# input.net
KiCad netlist of a schematic drawn in Altium Designer
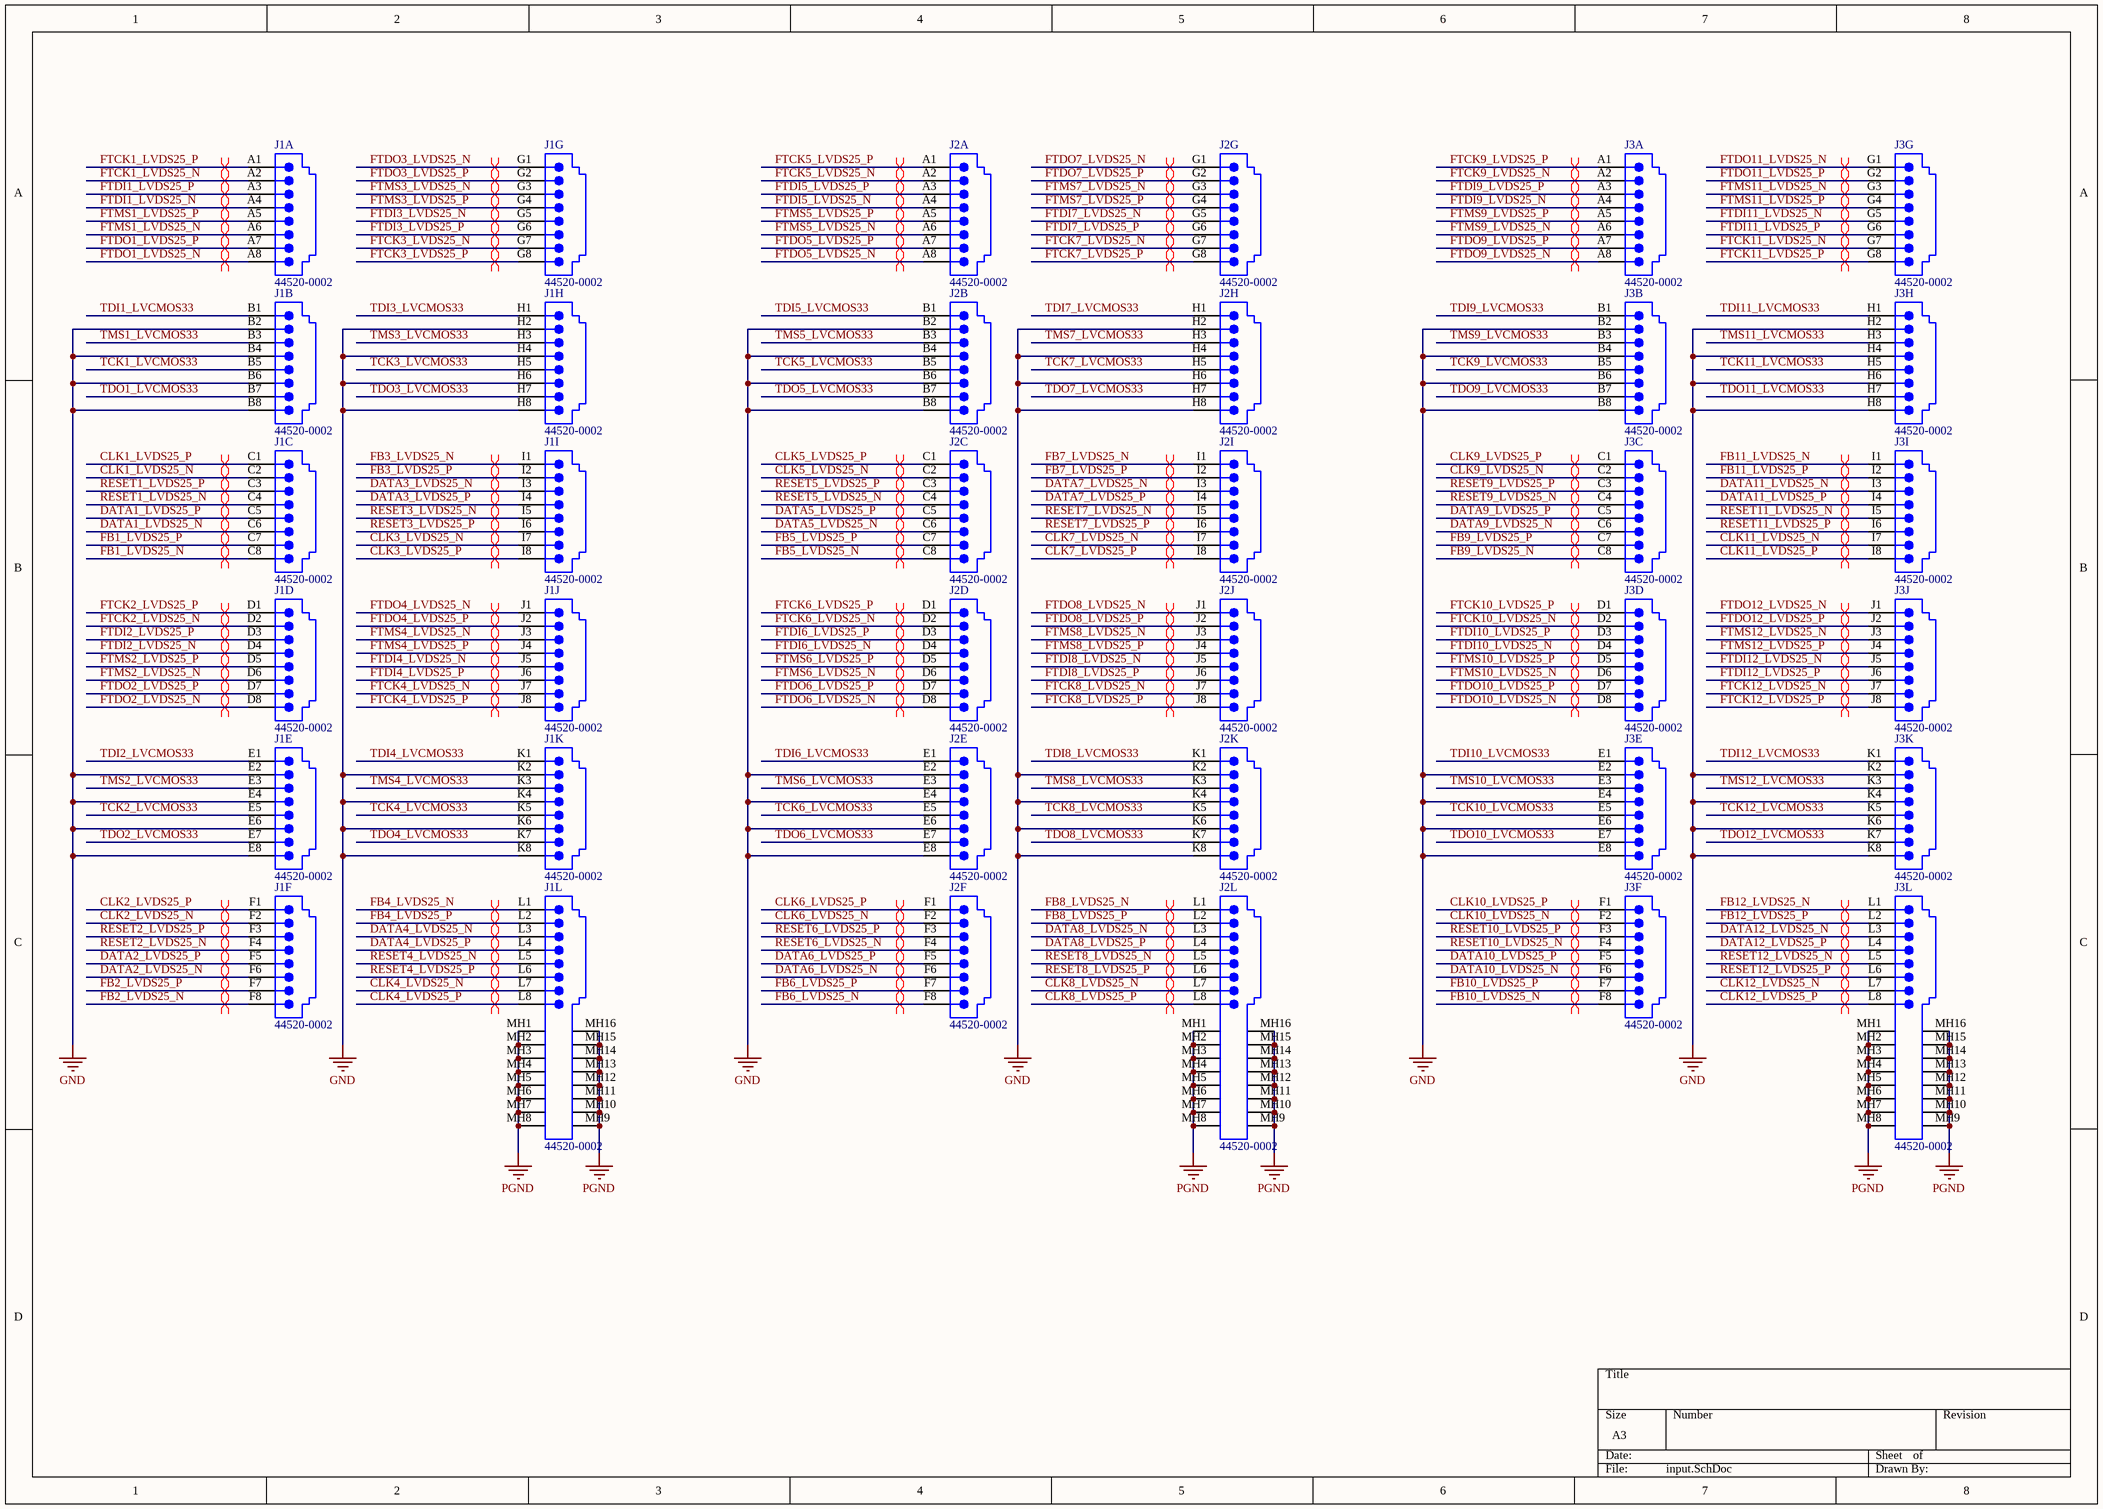
[diagram p0: input.SchDoc]

(export (version "E")
  (design (tool "Eeschema 10.0.6"))
  (components
    (comp (ref "J1")
      (value "44520-0002")
      (footprint "44520-0002")
      (description "High Speed, Stacked, Multi-Port, Right Angle, Snap-Fit, Shielded, Modular Jack")
      (fields (field (name "PUBLISHER") "Altium Limited"))
      (libsource (lib "RJ45大全") (part "44520-0002"))
    )
    (comp (ref "J2")
      (value "44520-0002")
      (footprint "44520-0002")
      (description "High Speed, Stacked, Multi-Port, Right Angle, Snap-Fit, Shielded, Modular Jack")
      (fields (field (name "PUBLISHER") "Altium Limited"))
      (libsource (lib "RJ45大全") (part "44520-0002"))
    )
    (comp (ref "J3")
      (value "44520-0002")
      (footprint "44520-0002")
      (description "High Speed, Stacked, Multi-Port, Right Angle, Snap-Fit, Shielded, Modular Jack")
      (fields (field (name "PUBLISHER") "Altium Limited"))
      (libsource (lib "RJ45大全") (part "44520-0002"))
    )
  )
  (nets
    (net (code "1") (name "/CLK1_LVDS25_N") (class "Default")
      (node (ref "J1") (pin "C2") (pinfunction "C2_C2") (pintype "passive"))
    )
    (net (code "2") (name "/CLK1_LVDS25_P") (class "Default")
      (node (ref "J1") (pin "C1") (pinfunction "C1_C1") (pintype "passive"))
    )
    (net (code "3") (name "/CLK2_LVDS25_N") (class "Default")
      (node (ref "J1") (pin "F2") (pinfunction "F2_F2") (pintype "passive"))
    )
    (net (code "4") (name "/CLK2_LVDS25_P") (class "Default")
      (node (ref "J1") (pin "F1") (pinfunction "F1_F1") (pintype "passive"))
    )
    (net (code "5") (name "/CLK3_LVDS25_N") (class "Default")
      (node (ref "J1") (pin "I7") (pinfunction "I7_I7") (pintype "passive"))
    )
    (net (code "6") (name "/CLK3_LVDS25_P") (class "Default")
      (node (ref "J1") (pin "I8") (pinfunction "I8_I8") (pintype "passive"))
    )
    (net (code "7") (name "/CLK4_LVDS25_N") (class "Default")
      (node (ref "J1") (pin "L7") (pinfunction "L7_L7") (pintype "passive"))
    )
    (net (code "8") (name "/CLK4_LVDS25_P") (class "Default")
      (node (ref "J1") (pin "L8") (pinfunction "L8_L8") (pintype "passive"))
    )
    (net (code "9") (name "/CLK5_LVDS25_N") (class "Default")
      (node (ref "J2") (pin "C2") (pinfunction "C2_C2") (pintype "passive"))
    )
    (net (code "10") (name "/CLK5_LVDS25_P") (class "Default")
      (node (ref "J2") (pin "C1") (pinfunction "C1_C1") (pintype "passive"))
    )
    (net (code "11") (name "/CLK6_LVDS25_N") (class "Default")
      (node (ref "J2") (pin "F2") (pinfunction "F2_F2") (pintype "passive"))
    )
    (net (code "12") (name "/CLK6_LVDS25_P") (class "Default")
      (node (ref "J2") (pin "F1") (pinfunction "F1_F1") (pintype "passive"))
    )
    (net (code "13") (name "/CLK7_LVDS25_N") (class "Default")
      (node (ref "J2") (pin "I7") (pinfunction "I7_I7") (pintype "passive"))
    )
    (net (code "14") (name "/CLK7_LVDS25_P") (class "Default")
      (node (ref "J2") (pin "I8") (pinfunction "I8_I8") (pintype "passive"))
    )
    (net (code "15") (name "/CLK8_LVDS25_N") (class "Default")
      (node (ref "J2") (pin "L7") (pinfunction "L7_L7") (pintype "passive"))
    )
    (net (code "16") (name "/CLK8_LVDS25_P") (class "Default")
      (node (ref "J2") (pin "L8") (pinfunction "L8_L8") (pintype "passive"))
    )
    (net (code "17") (name "/CLK9_LVDS25_N") (class "Default")
      (node (ref "J3") (pin "C2") (pinfunction "C2_C2") (pintype "passive"))
    )
    (net (code "18") (name "/CLK9_LVDS25_P") (class "Default")
      (node (ref "J3") (pin "C1") (pinfunction "C1_C1") (pintype "passive"))
    )
    (net (code "19") (name "/CLK10_LVDS25_N") (class "Default")
      (node (ref "J3") (pin "F2") (pinfunction "F2_F2") (pintype "passive"))
    )
    (net (code "20") (name "/CLK10_LVDS25_P") (class "Default")
      (node (ref "J3") (pin "F1") (pinfunction "F1_F1") (pintype "passive"))
    )
    (net (code "21") (name "/CLK11_LVDS25_N") (class "Default")
      (node (ref "J3") (pin "I7") (pinfunction "I7_I7") (pintype "passive"))
    )
    (net (code "22") (name "/CLK11_LVDS25_P") (class "Default")
      (node (ref "J3") (pin "I8") (pinfunction "I8_I8") (pintype "passive"))
    )
    (net (code "23") (name "/CLK12_LVDS25_N") (class "Default")
      (node (ref "J3") (pin "L7") (pinfunction "L7_L7") (pintype "passive"))
    )
    (net (code "24") (name "/CLK12_LVDS25_P") (class "Default")
      (node (ref "J3") (pin "L8") (pinfunction "L8_L8") (pintype "passive"))
    )
    (net (code "25") (name "/DATA1_LVDS25_N") (class "Default")
      (node (ref "J1") (pin "C6") (pinfunction "C6_C6") (pintype "passive"))
    )
    (net (code "26") (name "/DATA1_LVDS25_P") (class "Default")
      (node (ref "J1") (pin "C5") (pinfunction "C5_C5") (pintype "passive"))
    )
    (net (code "27") (name "/DATA2_LVDS25_N") (class "Default")
      (node (ref "J1") (pin "F6") (pinfunction "F6_F6") (pintype "passive"))
    )
    (net (code "28") (name "/DATA2_LVDS25_P") (class "Default")
      (node (ref "J1") (pin "F5") (pinfunction "F5_F5") (pintype "passive"))
    )
    (net (code "29") (name "/DATA3_LVDS25_N") (class "Default")
      (node (ref "J1") (pin "I3") (pinfunction "I3_I3") (pintype "passive"))
    )
    (net (code "30") (name "/DATA3_LVDS25_P") (class "Default")
      (node (ref "J1") (pin "I4") (pinfunction "I4_I4") (pintype "passive"))
    )
    (net (code "31") (name "/DATA4_LVDS25_N") (class "Default")
      (node (ref "J1") (pin "L3") (pinfunction "L3_L3") (pintype "passive"))
    )
    (net (code "32") (name "/DATA4_LVDS25_P") (class "Default")
      (node (ref "J1") (pin "L4") (pinfunction "L4_L4") (pintype "passive"))
    )
    (net (code "33") (name "/DATA5_LVDS25_N") (class "Default")
      (node (ref "J2") (pin "C6") (pinfunction "C6_C6") (pintype "passive"))
    )
    (net (code "34") (name "/DATA5_LVDS25_P") (class "Default")
      (node (ref "J2") (pin "C5") (pinfunction "C5_C5") (pintype "passive"))
    )
    (net (code "35") (name "/DATA6_LVDS25_N") (class "Default")
      (node (ref "J2") (pin "F6") (pinfunction "F6_F6") (pintype "passive"))
    )
    (net (code "36") (name "/DATA6_LVDS25_P") (class "Default")
      (node (ref "J2") (pin "F5") (pinfunction "F5_F5") (pintype "passive"))
    )
    (net (code "37") (name "/DATA7_LVDS25_N") (class "Default")
      (node (ref "J2") (pin "I3") (pinfunction "I3_I3") (pintype "passive"))
    )
    (net (code "38") (name "/DATA7_LVDS25_P") (class "Default")
      (node (ref "J2") (pin "I4") (pinfunction "I4_I4") (pintype "passive"))
    )
    (net (code "39") (name "/DATA8_LVDS25_N") (class "Default")
      (node (ref "J2") (pin "L3") (pinfunction "L3_L3") (pintype "passive"))
    )
    (net (code "40") (name "/DATA8_LVDS25_P") (class "Default")
      (node (ref "J2") (pin "L4") (pinfunction "L4_L4") (pintype "passive"))
    )
    (net (code "41") (name "/DATA9_LVDS25_N") (class "Default")
      (node (ref "J3") (pin "C6") (pinfunction "C6_C6") (pintype "passive"))
    )
    (net (code "42") (name "/DATA9_LVDS25_P") (class "Default")
      (node (ref "J3") (pin "C5") (pinfunction "C5_C5") (pintype "passive"))
    )
    (net (code "43") (name "/DATA10_LVDS25_N") (class "Default")
      (node (ref "J3") (pin "F6") (pinfunction "F6_F6") (pintype "passive"))
    )
    (net (code "44") (name "/DATA10_LVDS25_P") (class "Default")
      (node (ref "J3") (pin "F5") (pinfunction "F5_F5") (pintype "passive"))
    )
    (net (code "45") (name "/DATA11_LVDS25_N") (class "Default")
      (node (ref "J3") (pin "I3") (pinfunction "I3_I3") (pintype "passive"))
    )
    (net (code "46") (name "/DATA11_LVDS25_P") (class "Default")
      (node (ref "J3") (pin "I4") (pinfunction "I4_I4") (pintype "passive"))
    )
    (net (code "47") (name "/DATA12_LVDS25_N") (class "Default")
      (node (ref "J3") (pin "L3") (pinfunction "L3_L3") (pintype "passive"))
    )
    (net (code "48") (name "/DATA12_LVDS25_P") (class "Default")
      (node (ref "J3") (pin "L4") (pinfunction "L4_L4") (pintype "passive"))
    )
    (net (code "49") (name "/FB1_LVDS25_N") (class "Default")
      (node (ref "J1") (pin "C8") (pinfunction "C8_C8") (pintype "passive"))
    )
    (net (code "50") (name "/FB1_LVDS25_P") (class "Default")
      (node (ref "J1") (pin "C7") (pinfunction "C7_C7") (pintype "passive"))
    )
    (net (code "51") (name "/FB2_LVDS25_N") (class "Default")
      (node (ref "J1") (pin "F8") (pinfunction "F8_F8") (pintype "passive"))
    )
    (net (code "52") (name "/FB2_LVDS25_P") (class "Default")
      (node (ref "J1") (pin "F7") (pinfunction "F7_F7") (pintype "passive"))
    )
    (net (code "53") (name "/FB3_LVDS25_N") (class "Default")
      (node (ref "J1") (pin "I1") (pinfunction "I1_I1") (pintype "passive"))
    )
    (net (code "54") (name "/FB3_LVDS25_P") (class "Default")
      (node (ref "J1") (pin "I2") (pinfunction "I2_I2") (pintype "passive"))
    )
    (net (code "55") (name "/FB4_LVDS25_N") (class "Default")
      (node (ref "J1") (pin "L1") (pinfunction "L1_L1") (pintype "passive"))
    )
    (net (code "56") (name "/FB4_LVDS25_P") (class "Default")
      (node (ref "J1") (pin "L2") (pinfunction "L2_L2") (pintype "passive"))
    )
    (net (code "57") (name "/FB5_LVDS25_N") (class "Default")
      (node (ref "J2") (pin "C8") (pinfunction "C8_C8") (pintype "passive"))
    )
    (net (code "58") (name "/FB5_LVDS25_P") (class "Default")
      (node (ref "J2") (pin "C7") (pinfunction "C7_C7") (pintype "passive"))
    )
    (net (code "59") (name "/FB6_LVDS25_N") (class "Default")
      (node (ref "J2") (pin "F8") (pinfunction "F8_F8") (pintype "passive"))
    )
    (net (code "60") (name "/FB6_LVDS25_P") (class "Default")
      (node (ref "J2") (pin "F7") (pinfunction "F7_F7") (pintype "passive"))
    )
    (net (code "61") (name "/FB7_LVDS25_N") (class "Default")
      (node (ref "J2") (pin "I1") (pinfunction "I1_I1") (pintype "passive"))
    )
    (net (code "62") (name "/FB7_LVDS25_P") (class "Default")
      (node (ref "J2") (pin "I2") (pinfunction "I2_I2") (pintype "passive"))
    )
    (net (code "63") (name "/FB8_LVDS25_N") (class "Default")
      (node (ref "J2") (pin "L1") (pinfunction "L1_L1") (pintype "passive"))
    )
    (net (code "64") (name "/FB8_LVDS25_P") (class "Default")
      (node (ref "J2") (pin "L2") (pinfunction "L2_L2") (pintype "passive"))
    )
    (net (code "65") (name "/FB9_LVDS25_N") (class "Default")
      (node (ref "J3") (pin "C8") (pinfunction "C8_C8") (pintype "passive"))
    )
    (net (code "66") (name "/FB9_LVDS25_P") (class "Default")
      (node (ref "J3") (pin "C7") (pinfunction "C7_C7") (pintype "passive"))
    )
    (net (code "67") (name "/FB10_LVDS25_N") (class "Default")
      (node (ref "J3") (pin "F8") (pinfunction "F8_F8") (pintype "passive"))
    )
    (net (code "68") (name "/FB10_LVDS25_P") (class "Default")
      (node (ref "J3") (pin "F7") (pinfunction "F7_F7") (pintype "passive"))
    )
    (net (code "69") (name "/FB11_LVDS25_N") (class "Default")
      (node (ref "J3") (pin "I1") (pinfunction "I1_I1") (pintype "passive"))
    )
    (net (code "70") (name "/FB11_LVDS25_P") (class "Default")
      (node (ref "J3") (pin "I2") (pinfunction "I2_I2") (pintype "passive"))
    )
    (net (code "71") (name "/FB12_LVDS25_N") (class "Default")
      (node (ref "J3") (pin "L1") (pinfunction "L1_L1") (pintype "passive"))
    )
    (net (code "72") (name "/FB12_LVDS25_P") (class "Default")
      (node (ref "J3") (pin "L2") (pinfunction "L2_L2") (pintype "passive"))
    )
    (net (code "73") (name "/FTCK1_LVDS25_N") (class "Default")
      (node (ref "J1") (pin "A2") (pinfunction "A2_A2") (pintype "passive"))
    )
    (net (code "74") (name "/FTCK1_LVDS25_P") (class "Default")
      (node (ref "J1") (pin "A1") (pinfunction "A1_A1") (pintype "passive"))
    )
    (net (code "75") (name "/FTCK2_LVDS25_N") (class "Default")
      (node (ref "J1") (pin "D2") (pinfunction "D2_D2") (pintype "passive"))
    )
    (net (code "76") (name "/FTCK2_LVDS25_P") (class "Default")
      (node (ref "J1") (pin "D1") (pinfunction "D1_D1") (pintype "passive"))
    )
    (net (code "77") (name "/FTCK3_LVDS25_N") (class "Default")
      (node (ref "J1") (pin "G7") (pinfunction "G7_G7") (pintype "passive"))
    )
    (net (code "78") (name "/FTCK3_LVDS25_P") (class "Default")
      (node (ref "J1") (pin "G8") (pinfunction "G8_G8") (pintype "passive"))
    )
    (net (code "79") (name "/FTCK4_LVDS25_N") (class "Default")
      (node (ref "J1") (pin "J7") (pinfunction "J7_J7") (pintype "passive"))
    )
    (net (code "80") (name "/FTCK4_LVDS25_P") (class "Default")
      (node (ref "J1") (pin "J8") (pinfunction "J8_J8") (pintype "passive"))
    )
    (net (code "81") (name "/FTCK5_LVDS25_N") (class "Default")
      (node (ref "J2") (pin "A2") (pinfunction "A2_A2") (pintype "passive"))
    )
    (net (code "82") (name "/FTCK5_LVDS25_P") (class "Default")
      (node (ref "J2") (pin "A1") (pinfunction "A1_A1") (pintype "passive"))
    )
    (net (code "83") (name "/FTCK6_LVDS25_N") (class "Default")
      (node (ref "J2") (pin "D2") (pinfunction "D2_D2") (pintype "passive"))
    )
    (net (code "84") (name "/FTCK6_LVDS25_P") (class "Default")
      (node (ref "J2") (pin "D1") (pinfunction "D1_D1") (pintype "passive"))
    )
    (net (code "85") (name "/FTCK7_LVDS25_N") (class "Default")
      (node (ref "J2") (pin "G7") (pinfunction "G7_G7") (pintype "passive"))
    )
    (net (code "86") (name "/FTCK7_LVDS25_P") (class "Default")
      (node (ref "J2") (pin "G8") (pinfunction "G8_G8") (pintype "passive"))
    )
    (net (code "87") (name "/FTCK8_LVDS25_N") (class "Default")
      (node (ref "J2") (pin "J7") (pinfunction "J7_J7") (pintype "passive"))
    )
    (net (code "88") (name "/FTCK8_LVDS25_P") (class "Default")
      (node (ref "J2") (pin "J8") (pinfunction "J8_J8") (pintype "passive"))
    )
    (net (code "89") (name "/FTCK9_LVDS25_N") (class "Default")
      (node (ref "J3") (pin "A2") (pinfunction "A2_A2") (pintype "passive"))
    )
    (net (code "90") (name "/FTCK9_LVDS25_P") (class "Default")
      (node (ref "J3") (pin "A1") (pinfunction "A1_A1") (pintype "passive"))
    )
    (net (code "91") (name "/FTCK10_LVDS25_N") (class "Default")
      (node (ref "J3") (pin "D2") (pinfunction "D2_D2") (pintype "passive"))
    )
    (net (code "92") (name "/FTCK10_LVDS25_P") (class "Default")
      (node (ref "J3") (pin "D1") (pinfunction "D1_D1") (pintype "passive"))
    )
    (net (code "93") (name "/FTCK11_LVDS25_N") (class "Default")
      (node (ref "J3") (pin "G7") (pinfunction "G7_G7") (pintype "passive"))
    )
    (net (code "94") (name "/FTCK11_LVDS25_P") (class "Default")
      (node (ref "J3") (pin "G8") (pinfunction "G8_G8") (pintype "passive"))
    )
    (net (code "95") (name "/FTCK12_LVDS25_N") (class "Default")
      (node (ref "J3") (pin "J7") (pinfunction "J7_J7") (pintype "passive"))
    )
    (net (code "96") (name "/FTCK12_LVDS25_P") (class "Default")
      (node (ref "J3") (pin "J8") (pinfunction "J8_J8") (pintype "passive"))
    )
    (net (code "97") (name "/FTDI1_LVDS25_N") (class "Default")
      (node (ref "J1") (pin "A4") (pinfunction "A4_A4") (pintype "passive"))
    )
    (net (code "98") (name "/FTDI1_LVDS25_P") (class "Default")
      (node (ref "J1") (pin "A3") (pinfunction "A3_A3") (pintype "passive"))
    )
    (net (code "99") (name "/FTDI2_LVDS25_N") (class "Default")
      (node (ref "J1") (pin "D4") (pinfunction "D4_D4") (pintype "passive"))
    )
    (net (code "100") (name "/FTDI2_LVDS25_P") (class "Default")
      (node (ref "J1") (pin "D3") (pinfunction "D3_D3") (pintype "passive"))
    )
    (net (code "101") (name "/FTDI3_LVDS25_N") (class "Default")
      (node (ref "J1") (pin "G5") (pinfunction "G5_G5") (pintype "passive"))
    )
    (net (code "102") (name "/FTDI3_LVDS25_P") (class "Default")
      (node (ref "J1") (pin "G6") (pinfunction "G6_G6") (pintype "passive"))
    )
    (net (code "103") (name "/FTDI4_LVDS25_N") (class "Default")
      (node (ref "J1") (pin "J5") (pinfunction "J5_J5") (pintype "passive"))
    )
    (net (code "104") (name "/FTDI4_LVDS25_P") (class "Default")
      (node (ref "J1") (pin "J6") (pinfunction "J6_J6") (pintype "passive"))
    )
    (net (code "105") (name "/FTDI5_LVDS25_N") (class "Default")
      (node (ref "J2") (pin "A4") (pinfunction "A4_A4") (pintype "passive"))
    )
    (net (code "106") (name "/FTDI5_LVDS25_P") (class "Default")
      (node (ref "J2") (pin "A3") (pinfunction "A3_A3") (pintype "passive"))
    )
    (net (code "107") (name "/FTDI6_LVDS25_N") (class "Default")
      (node (ref "J2") (pin "D4") (pinfunction "D4_D4") (pintype "passive"))
    )
    (net (code "108") (name "/FTDI6_LVDS25_P") (class "Default")
      (node (ref "J2") (pin "D3") (pinfunction "D3_D3") (pintype "passive"))
    )
    (net (code "109") (name "/FTDI7_LVDS25_N") (class "Default")
      (node (ref "J2") (pin "G5") (pinfunction "G5_G5") (pintype "passive"))
    )
    (net (code "110") (name "/FTDI7_LVDS25_P") (class "Default")
      (node (ref "J2") (pin "G6") (pinfunction "G6_G6") (pintype "passive"))
    )
    (net (code "111") (name "/FTDI8_LVDS25_N") (class "Default")
      (node (ref "J2") (pin "J5") (pinfunction "J5_J5") (pintype "passive"))
    )
    (net (code "112") (name "/FTDI8_LVDS25_P") (class "Default")
      (node (ref "J2") (pin "J6") (pinfunction "J6_J6") (pintype "passive"))
    )
    (net (code "113") (name "/FTDI9_LVDS25_N") (class "Default")
      (node (ref "J3") (pin "A4") (pinfunction "A4_A4") (pintype "passive"))
    )
    (net (code "114") (name "/FTDI9_LVDS25_P") (class "Default")
      (node (ref "J3") (pin "A3") (pinfunction "A3_A3") (pintype "passive"))
    )
    (net (code "115") (name "/FTDI10_LVDS25_N") (class "Default")
      (node (ref "J3") (pin "D4") (pinfunction "D4_D4") (pintype "passive"))
    )
    (net (code "116") (name "/FTDI10_LVDS25_P") (class "Default")
      (node (ref "J3") (pin "D3") (pinfunction "D3_D3") (pintype "passive"))
    )
    (net (code "117") (name "/FTDI11_LVDS25_N") (class "Default")
      (node (ref "J3") (pin "G5") (pinfunction "G5_G5") (pintype "passive"))
    )
    (net (code "118") (name "/FTDI11_LVDS25_P") (class "Default")
      (node (ref "J3") (pin "G6") (pinfunction "G6_G6") (pintype "passive"))
    )
    (net (code "119") (name "/FTDI12_LVDS25_N") (class "Default")
      (node (ref "J3") (pin "J5") (pinfunction "J5_J5") (pintype "passive"))
    )
    (net (code "120") (name "/FTDI12_LVDS25_P") (class "Default")
      (node (ref "J3") (pin "J6") (pinfunction "J6_J6") (pintype "passive"))
    )
    (net (code "121") (name "/FTDO1_LVDS25_N") (class "Default")
      (node (ref "J1") (pin "A8") (pinfunction "A8_A8") (pintype "passive"))
    )
    (net (code "122") (name "/FTDO1_LVDS25_P") (class "Default")
      (node (ref "J1") (pin "A7") (pinfunction "A7_A7") (pintype "passive"))
    )
    (net (code "123") (name "/FTDO2_LVDS25_N") (class "Default")
      (node (ref "J1") (pin "D8") (pinfunction "D8_D8") (pintype "passive"))
    )
    (net (code "124") (name "/FTDO2_LVDS25_P") (class "Default")
      (node (ref "J1") (pin "D7") (pinfunction "D7_D7") (pintype "passive"))
    )
    (net (code "125") (name "/FTDO3_LVDS25_N") (class "Default")
      (node (ref "J1") (pin "G1") (pinfunction "G1_G1") (pintype "passive"))
    )
    (net (code "126") (name "/FTDO3_LVDS25_P") (class "Default")
      (node (ref "J1") (pin "G2") (pinfunction "G2_G2") (pintype "passive"))
    )
    (net (code "127") (name "/FTDO4_LVDS25_N") (class "Default")
      (node (ref "J1") (pin "J1") (pinfunction "J1_J1") (pintype "passive"))
    )
    (net (code "128") (name "/FTDO4_LVDS25_P") (class "Default")
      (node (ref "J1") (pin "J2") (pinfunction "J2_J2") (pintype "passive"))
    )
    (net (code "129") (name "/FTDO5_LVDS25_N") (class "Default")
      (node (ref "J2") (pin "A8") (pinfunction "A8_A8") (pintype "passive"))
    )
    (net (code "130") (name "/FTDO5_LVDS25_P") (class "Default")
      (node (ref "J2") (pin "A7") (pinfunction "A7_A7") (pintype "passive"))
    )
    (net (code "131") (name "/FTDO6_LVDS25_N") (class "Default")
      (node (ref "J2") (pin "D8") (pinfunction "D8_D8") (pintype "passive"))
    )
    (net (code "132") (name "/FTDO6_LVDS25_P") (class "Default")
      (node (ref "J2") (pin "D7") (pinfunction "D7_D7") (pintype "passive"))
    )
    (net (code "133") (name "/FTDO7_LVDS25_N") (class "Default")
      (node (ref "J2") (pin "G1") (pinfunction "G1_G1") (pintype "passive"))
    )
    (net (code "134") (name "/FTDO7_LVDS25_P") (class "Default")
      (node (ref "J2") (pin "G2") (pinfunction "G2_G2") (pintype "passive"))
    )
    (net (code "135") (name "/FTDO8_LVDS25_N") (class "Default")
      (node (ref "J2") (pin "J1") (pinfunction "J1_J1") (pintype "passive"))
    )
    (net (code "136") (name "/FTDO8_LVDS25_P") (class "Default")
      (node (ref "J2") (pin "J2") (pinfunction "J2_J2") (pintype "passive"))
    )
    (net (code "137") (name "/FTDO9_LVDS25_N") (class "Default")
      (node (ref "J3") (pin "A8") (pinfunction "A8_A8") (pintype "passive"))
    )
    (net (code "138") (name "/FTDO9_LVDS25_P") (class "Default")
      (node (ref "J3") (pin "A7") (pinfunction "A7_A7") (pintype "passive"))
    )
    (net (code "139") (name "/FTDO10_LVDS25_N") (class "Default")
      (node (ref "J3") (pin "D8") (pinfunction "D8_D8") (pintype "passive"))
    )
    (net (code "140") (name "/FTDO10_LVDS25_P") (class "Default")
      (node (ref "J3") (pin "D7") (pinfunction "D7_D7") (pintype "passive"))
    )
    (net (code "141") (name "/FTDO11_LVDS25_N") (class "Default")
      (node (ref "J3") (pin "G1") (pinfunction "G1_G1") (pintype "passive"))
    )
    (net (code "142") (name "/FTDO11_LVDS25_P") (class "Default")
      (node (ref "J3") (pin "G2") (pinfunction "G2_G2") (pintype "passive"))
    )
    (net (code "143") (name "/FTDO12_LVDS25_N") (class "Default")
      (node (ref "J3") (pin "J1") (pinfunction "J1_J1") (pintype "passive"))
    )
    (net (code "144") (name "/FTDO12_LVDS25_P") (class "Default")
      (node (ref "J3") (pin "J2") (pinfunction "J2_J2") (pintype "passive"))
    )
    (net (code "145") (name "/FTMS1_LVDS25_N") (class "Default")
      (node (ref "J1") (pin "A6") (pinfunction "A6_A6") (pintype "passive"))
    )
    (net (code "146") (name "/FTMS1_LVDS25_P") (class "Default")
      (node (ref "J1") (pin "A5") (pinfunction "A5_A5") (pintype "passive"))
    )
    (net (code "147") (name "/FTMS2_LVDS25_N") (class "Default")
      (node (ref "J1") (pin "D6") (pinfunction "D6_D6") (pintype "passive"))
    )
    (net (code "148") (name "/FTMS2_LVDS25_P") (class "Default")
      (node (ref "J1") (pin "D5") (pinfunction "D5_D5") (pintype "passive"))
    )
    (net (code "149") (name "/FTMS3_LVDS25_N") (class "Default")
      (node (ref "J1") (pin "G3") (pinfunction "G3_G3") (pintype "passive"))
    )
    (net (code "150") (name "/FTMS3_LVDS25_P") (class "Default")
      (node (ref "J1") (pin "G4") (pinfunction "G4_G4") (pintype "passive"))
    )
    (net (code "151") (name "/FTMS4_LVDS25_N") (class "Default")
      (node (ref "J1") (pin "J3") (pinfunction "J3_J3") (pintype "passive"))
    )
    (net (code "152") (name "/FTMS4_LVDS25_P") (class "Default")
      (node (ref "J1") (pin "J4") (pinfunction "J4_J4") (pintype "passive"))
    )
    (net (code "153") (name "/FTMS5_LVDS25_N") (class "Default")
      (node (ref "J2") (pin "A6") (pinfunction "A6_A6") (pintype "passive"))
    )
    (net (code "154") (name "/FTMS5_LVDS25_P") (class "Default")
      (node (ref "J2") (pin "A5") (pinfunction "A5_A5") (pintype "passive"))
    )
    (net (code "155") (name "/FTMS6_LVDS25_N") (class "Default")
      (node (ref "J2") (pin "D6") (pinfunction "D6_D6") (pintype "passive"))
    )
    (net (code "156") (name "/FTMS6_LVDS25_P") (class "Default")
      (node (ref "J2") (pin "D5") (pinfunction "D5_D5") (pintype "passive"))
    )
    (net (code "157") (name "/FTMS7_LVDS25_N") (class "Default")
      (node (ref "J2") (pin "G3") (pinfunction "G3_G3") (pintype "passive"))
    )
    (net (code "158") (name "/FTMS7_LVDS25_P") (class "Default")
      (node (ref "J2") (pin "G4") (pinfunction "G4_G4") (pintype "passive"))
    )
    (net (code "159") (name "/FTMS8_LVDS25_N") (class "Default")
      (node (ref "J2") (pin "J3") (pinfunction "J3_J3") (pintype "passive"))
    )
    (net (code "160") (name "/FTMS8_LVDS25_P") (class "Default")
      (node (ref "J2") (pin "J4") (pinfunction "J4_J4") (pintype "passive"))
    )
    (net (code "161") (name "/FTMS9_LVDS25_N") (class "Default")
      (node (ref "J3") (pin "A6") (pinfunction "A6_A6") (pintype "passive"))
    )
    (net (code "162") (name "/FTMS9_LVDS25_P") (class "Default")
      (node (ref "J3") (pin "A5") (pinfunction "A5_A5") (pintype "passive"))
    )
    (net (code "163") (name "/FTMS10_LVDS25_N") (class "Default")
      (node (ref "J3") (pin "D6") (pinfunction "D6_D6") (pintype "passive"))
    )
    (net (code "164") (name "/FTMS10_LVDS25_P") (class "Default")
      (node (ref "J3") (pin "D5") (pinfunction "D5_D5") (pintype "passive"))
    )
    (net (code "165") (name "/FTMS11_LVDS25_N") (class "Default")
      (node (ref "J3") (pin "G3") (pinfunction "G3_G3") (pintype "passive"))
    )
    (net (code "166") (name "/FTMS11_LVDS25_P") (class "Default")
      (node (ref "J3") (pin "G4") (pinfunction "G4_G4") (pintype "passive"))
    )
    (net (code "167") (name "/FTMS12_LVDS25_N") (class "Default")
      (node (ref "J3") (pin "J3") (pinfunction "J3_J3") (pintype "passive"))
    )
    (net (code "168") (name "/FTMS12_LVDS25_P") (class "Default")
      (node (ref "J3") (pin "J4") (pinfunction "J4_J4") (pintype "passive"))
    )
    (net (code "169") (name "/RESET1_LVDS25_N") (class "Default")
      (node (ref "J1") (pin "C4") (pinfunction "C4_C4") (pintype "passive"))
    )
    (net (code "170") (name "/RESET1_LVDS25_P") (class "Default")
      (node (ref "J1") (pin "C3") (pinfunction "C3_C3") (pintype "passive"))
    )
    (net (code "171") (name "/RESET2_LVDS25_N") (class "Default")
      (node (ref "J1") (pin "F4") (pinfunction "F4_F4") (pintype "passive"))
    )
    (net (code "172") (name "/RESET2_LVDS25_P") (class "Default")
      (node (ref "J1") (pin "F3") (pinfunction "F3_F3") (pintype "passive"))
    )
    (net (code "173") (name "/RESET3_LVDS25_N") (class "Default")
      (node (ref "J1") (pin "I5") (pinfunction "I5_I5") (pintype "passive"))
    )
    (net (code "174") (name "/RESET3_LVDS25_P") (class "Default")
      (node (ref "J1") (pin "I6") (pinfunction "I6_I6") (pintype "passive"))
    )
    (net (code "175") (name "/RESET4_LVDS25_N") (class "Default")
      (node (ref "J1") (pin "L5") (pinfunction "L5_L5") (pintype "passive"))
    )
    (net (code "176") (name "/RESET4_LVDS25_P") (class "Default")
      (node (ref "J1") (pin "L6") (pinfunction "L6_L6") (pintype "passive"))
    )
    (net (code "177") (name "/RESET5_LVDS25_N") (class "Default")
      (node (ref "J2") (pin "C4") (pinfunction "C4_C4") (pintype "passive"))
    )
    (net (code "178") (name "/RESET5_LVDS25_P") (class "Default")
      (node (ref "J2") (pin "C3") (pinfunction "C3_C3") (pintype "passive"))
    )
    (net (code "179") (name "/RESET6_LVDS25_N") (class "Default")
      (node (ref "J2") (pin "F4") (pinfunction "F4_F4") (pintype "passive"))
    )
    (net (code "180") (name "/RESET6_LVDS25_P") (class "Default")
      (node (ref "J2") (pin "F3") (pinfunction "F3_F3") (pintype "passive"))
    )
    (net (code "181") (name "/RESET7_LVDS25_N") (class "Default")
      (node (ref "J2") (pin "I5") (pinfunction "I5_I5") (pintype "passive"))
    )
    (net (code "182") (name "/RESET7_LVDS25_P") (class "Default")
      (node (ref "J2") (pin "I6") (pinfunction "I6_I6") (pintype "passive"))
    )
    (net (code "183") (name "/RESET8_LVDS25_N") (class "Default")
      (node (ref "J2") (pin "L5") (pinfunction "L5_L5") (pintype "passive"))
    )
    (net (code "184") (name "/RESET8_LVDS25_P") (class "Default")
      (node (ref "J2") (pin "L6") (pinfunction "L6_L6") (pintype "passive"))
    )
    (net (code "185") (name "/RESET9_LVDS25_N") (class "Default")
      (node (ref "J3") (pin "C4") (pinfunction "C4_C4") (pintype "passive"))
    )
    (net (code "186") (name "/RESET9_LVDS25_P") (class "Default")
      (node (ref "J3") (pin "C3") (pinfunction "C3_C3") (pintype "passive"))
    )
    (net (code "187") (name "/RESET10_LVDS25_N") (class "Default")
      (node (ref "J3") (pin "F4") (pinfunction "F4_F4") (pintype "passive"))
    )
    (net (code "188") (name "/RESET10_LVDS25_P") (class "Default")
      (node (ref "J3") (pin "F3") (pinfunction "F3_F3") (pintype "passive"))
    )
    (net (code "189") (name "/RESET11_LVDS25_N") (class "Default")
      (node (ref "J3") (pin "I5") (pinfunction "I5_I5") (pintype "passive"))
    )
    (net (code "190") (name "/RESET11_LVDS25_P") (class "Default")
      (node (ref "J3") (pin "I6") (pinfunction "I6_I6") (pintype "passive"))
    )
    (net (code "191") (name "/RESET12_LVDS25_N") (class "Default")
      (node (ref "J3") (pin "L5") (pinfunction "L5_L5") (pintype "passive"))
    )
    (net (code "192") (name "/RESET12_LVDS25_P") (class "Default")
      (node (ref "J3") (pin "L6") (pinfunction "L6_L6") (pintype "passive"))
    )
    (net (code "193") (name "/TCK1_LVCMOS33") (class "Default")
      (node (ref "J1") (pin "B5") (pinfunction "B5_B5") (pintype "passive"))
    )
    (net (code "194") (name "/TCK2_LVCMOS33") (class "Default")
      (node (ref "J1") (pin "E5") (pinfunction "E5_E5") (pintype "passive"))
    )
    (net (code "195") (name "/TCK3_LVCMOS33") (class "Default")
      (node (ref "J1") (pin "H5") (pinfunction "H5_H5") (pintype "passive"))
    )
    (net (code "196") (name "/TCK4_LVCMOS33") (class "Default")
      (node (ref "J1") (pin "K5") (pinfunction "K5_K5") (pintype "passive"))
    )
    (net (code "197") (name "/TCK5_LVCMOS33") (class "Default")
      (node (ref "J2") (pin "B5") (pinfunction "B5_B5") (pintype "passive"))
    )
    (net (code "198") (name "/TCK6_LVCMOS33") (class "Default")
      (node (ref "J2") (pin "E5") (pinfunction "E5_E5") (pintype "passive"))
    )
    (net (code "199") (name "/TCK7_LVCMOS33") (class "Default")
      (node (ref "J2") (pin "H5") (pinfunction "H5_H5") (pintype "passive"))
    )
    (net (code "200") (name "/TCK8_LVCMOS33") (class "Default")
      (node (ref "J2") (pin "K5") (pinfunction "K5_K5") (pintype "passive"))
    )
    (net (code "201") (name "/TCK9_LVCMOS33") (class "Default")
      (node (ref "J3") (pin "B5") (pinfunction "B5_B5") (pintype "passive"))
    )
    (net (code "202") (name "/TCK10_LVCMOS33") (class "Default")
      (node (ref "J3") (pin "E5") (pinfunction "E5_E5") (pintype "passive"))
    )
    (net (code "203") (name "/TCK11_LVCMOS33") (class "Default")
      (node (ref "J3") (pin "H5") (pinfunction "H5_H5") (pintype "passive"))
    )
    (net (code "204") (name "/TCK12_LVCMOS33") (class "Default")
      (node (ref "J3") (pin "K5") (pinfunction "K5_K5") (pintype "passive"))
    )
    (net (code "205") (name "/TDI1_LVCMOS33") (class "Default")
      (node (ref "J1") (pin "B1") (pinfunction "B1_B1") (pintype "passive"))
    )
    (net (code "206") (name "/TDI2_LVCMOS33") (class "Default")
      (node (ref "J1") (pin "E1") (pinfunction "E1_E1") (pintype "passive"))
    )
    (net (code "207") (name "/TDI3_LVCMOS33") (class "Default")
      (node (ref "J1") (pin "H1") (pinfunction "H1_H1") (pintype "passive"))
    )
    (net (code "208") (name "/TDI4_LVCMOS33") (class "Default")
      (node (ref "J1") (pin "K1") (pinfunction "K1_K1") (pintype "passive"))
    )
    (net (code "209") (name "/TDI5_LVCMOS33") (class "Default")
      (node (ref "J2") (pin "B1") (pinfunction "B1_B1") (pintype "passive"))
    )
    (net (code "210") (name "/TDI6_LVCMOS33") (class "Default")
      (node (ref "J2") (pin "E1") (pinfunction "E1_E1") (pintype "passive"))
    )
    (net (code "211") (name "/TDI7_LVCMOS33") (class "Default")
      (node (ref "J2") (pin "H1") (pinfunction "H1_H1") (pintype "passive"))
    )
    (net (code "212") (name "/TDI8_LVCMOS33") (class "Default")
      (node (ref "J2") (pin "K1") (pinfunction "K1_K1") (pintype "passive"))
    )
    (net (code "213") (name "/TDI9_LVCMOS33") (class "Default")
      (node (ref "J3") (pin "B1") (pinfunction "B1_B1") (pintype "passive"))
    )
    (net (code "214") (name "/TDI10_LVCMOS33") (class "Default")
      (node (ref "J3") (pin "E1") (pinfunction "E1_E1") (pintype "passive"))
    )
    (net (code "215") (name "/TDI11_LVCMOS33") (class "Default")
      (node (ref "J3") (pin "H1") (pinfunction "H1_H1") (pintype "passive"))
    )
    (net (code "216") (name "/TDI12_LVCMOS33") (class "Default")
      (node (ref "J3") (pin "K1") (pinfunction "K1_K1") (pintype "passive"))
    )
    (net (code "217") (name "/TDO1_LVCMOS33") (class "Default")
      (node (ref "J1") (pin "B7") (pinfunction "B7_B7") (pintype "passive"))
    )
    (net (code "218") (name "/TDO2_LVCMOS33") (class "Default")
      (node (ref "J1") (pin "E7") (pinfunction "E7_E7") (pintype "passive"))
    )
    (net (code "219") (name "/TDO3_LVCMOS33") (class "Default")
      (node (ref "J1") (pin "H7") (pinfunction "H7_H7") (pintype "passive"))
    )
    (net (code "220") (name "/TDO4_LVCMOS33") (class "Default")
      (node (ref "J1") (pin "K7") (pinfunction "K7_K7") (pintype "passive"))
    )
    (net (code "221") (name "/TDO5_LVCMOS33") (class "Default")
      (node (ref "J2") (pin "B7") (pinfunction "B7_B7") (pintype "passive"))
    )
    (net (code "222") (name "/TDO6_LVCMOS33") (class "Default")
      (node (ref "J2") (pin "E7") (pinfunction "E7_E7") (pintype "passive"))
    )
    (net (code "223") (name "/TDO7_LVCMOS33") (class "Default")
      (node (ref "J2") (pin "H7") (pinfunction "H7_H7") (pintype "passive"))
    )
    (net (code "224") (name "/TDO8_LVCMOS33") (class "Default")
      (node (ref "J2") (pin "K7") (pinfunction "K7_K7") (pintype "passive"))
    )
    (net (code "225") (name "/TDO9_LVCMOS33") (class "Default")
      (node (ref "J3") (pin "B7") (pinfunction "B7_B7") (pintype "passive"))
    )
    (net (code "226") (name "/TDO10_LVCMOS33") (class "Default")
      (node (ref "J3") (pin "E7") (pinfunction "E7_E7") (pintype "passive"))
    )
    (net (code "227") (name "/TDO11_LVCMOS33") (class "Default")
      (node (ref "J3") (pin "H7") (pinfunction "H7_H7") (pintype "passive"))
    )
    (net (code "228") (name "/TDO12_LVCMOS33") (class "Default")
      (node (ref "J3") (pin "K7") (pinfunction "K7_K7") (pintype "passive"))
    )
    (net (code "229") (name "/TMS1_LVCMOS33") (class "Default")
      (node (ref "J1") (pin "B3") (pinfunction "B3_B3") (pintype "passive"))
    )
    (net (code "230") (name "/TMS2_LVCMOS33") (class "Default")
      (node (ref "J1") (pin "E3") (pinfunction "E3_E3") (pintype "passive"))
    )
    (net (code "231") (name "/TMS3_LVCMOS33") (class "Default")
      (node (ref "J1") (pin "H3") (pinfunction "H3_H3") (pintype "passive"))
    )
    (net (code "232") (name "/TMS4_LVCMOS33") (class "Default")
      (node (ref "J1") (pin "K3") (pinfunction "K3_K3") (pintype "passive"))
    )
    (net (code "233") (name "/TMS5_LVCMOS33") (class "Default")
      (node (ref "J2") (pin "B3") (pinfunction "B3_B3") (pintype "passive"))
    )
    (net (code "234") (name "/TMS6_LVCMOS33") (class "Default")
      (node (ref "J2") (pin "E3") (pinfunction "E3_E3") (pintype "passive"))
    )
    (net (code "235") (name "/TMS7_LVCMOS33") (class "Default")
      (node (ref "J2") (pin "H3") (pinfunction "H3_H3") (pintype "passive"))
    )
    (net (code "236") (name "/TMS8_LVCMOS33") (class "Default")
      (node (ref "J2") (pin "K3") (pinfunction "K3_K3") (pintype "passive"))
    )
    (net (code "237") (name "/TMS9_LVCMOS33") (class "Default")
      (node (ref "J3") (pin "B3") (pinfunction "B3_B3") (pintype "passive"))
    )
    (net (code "238") (name "/TMS10_LVCMOS33") (class "Default")
      (node (ref "J3") (pin "E3") (pinfunction "E3_E3") (pintype "passive"))
    )
    (net (code "239") (name "/TMS11_LVCMOS33") (class "Default")
      (node (ref "J3") (pin "H3") (pinfunction "H3_H3") (pintype "passive"))
    )
    (net (code "240") (name "/TMS12_LVCMOS33") (class "Default")
      (node (ref "J3") (pin "K3") (pinfunction "K3_K3") (pintype "passive"))
    )
    (net (code "241") (name "GND") (class "Default")
      (node (ref "J1") (pin "B2") (pinfunction "B2_B2") (pintype "passive"))
      (node (ref "J1") (pin "B4") (pinfunction "B4_B4") (pintype "passive"))
      (node (ref "J1") (pin "B6") (pinfunction "B6_B6") (pintype "passive"))
      (node (ref "J1") (pin "B8") (pinfunction "B8_B8") (pintype "passive"))
      (node (ref "J1") (pin "E2") (pinfunction "E2_E2") (pintype "passive"))
      (node (ref "J1") (pin "E4") (pinfunction "E4_E4") (pintype "passive"))
      (node (ref "J1") (pin "E6") (pinfunction "E6_E6") (pintype "passive"))
      (node (ref "J1") (pin "E8") (pinfunction "E8_E8") (pintype "passive"))
      (node (ref "J1") (pin "H2") (pinfunction "H2_H2") (pintype "passive"))
      (node (ref "J1") (pin "H4") (pinfunction "H4_H4") (pintype "passive"))
      (node (ref "J1") (pin "H6") (pinfunction "H6_H6") (pintype "passive"))
      (node (ref "J1") (pin "H8") (pinfunction "H8_H8") (pintype "passive"))
      (node (ref "J1") (pin "K2") (pinfunction "K2_K2") (pintype "passive"))
      (node (ref "J1") (pin "K4") (pinfunction "K4_K4") (pintype "passive"))
      (node (ref "J1") (pin "K6") (pinfunction "K6_K6") (pintype "passive"))
      (node (ref "J1") (pin "K8") (pinfunction "K8_K8") (pintype "passive"))
      (node (ref "J2") (pin "B2") (pinfunction "B2_B2") (pintype "passive"))
      (node (ref "J2") (pin "B4") (pinfunction "B4_B4") (pintype "passive"))
      (node (ref "J2") (pin "B6") (pinfunction "B6_B6") (pintype "passive"))
      (node (ref "J2") (pin "B8") (pinfunction "B8_B8") (pintype "passive"))
      (node (ref "J2") (pin "E2") (pinfunction "E2_E2") (pintype "passive"))
      (node (ref "J2") (pin "E4") (pinfunction "E4_E4") (pintype "passive"))
      (node (ref "J2") (pin "E6") (pinfunction "E6_E6") (pintype "passive"))
      (node (ref "J2") (pin "E8") (pinfunction "E8_E8") (pintype "passive"))
      (node (ref "J2") (pin "H2") (pinfunction "H2_H2") (pintype "passive"))
      (node (ref "J2") (pin "H4") (pinfunction "H4_H4") (pintype "passive"))
      (node (ref "J2") (pin "H6") (pinfunction "H6_H6") (pintype "passive"))
      (node (ref "J2") (pin "H8") (pinfunction "H8_H8") (pintype "passive"))
      (node (ref "J2") (pin "K2") (pinfunction "K2_K2") (pintype "passive"))
      (node (ref "J2") (pin "K4") (pinfunction "K4_K4") (pintype "passive"))
      (node (ref "J2") (pin "K6") (pinfunction "K6_K6") (pintype "passive"))
      (node (ref "J2") (pin "K8") (pinfunction "K8_K8") (pintype "passive"))
      (node (ref "J3") (pin "B2") (pinfunction "B2_B2") (pintype "passive"))
      (node (ref "J3") (pin "B4") (pinfunction "B4_B4") (pintype "passive"))
      (node (ref "J3") (pin "B6") (pinfunction "B6_B6") (pintype "passive"))
      (node (ref "J3") (pin "B8") (pinfunction "B8_B8") (pintype "passive"))
      (node (ref "J3") (pin "E2") (pinfunction "E2_E2") (pintype "passive"))
      (node (ref "J3") (pin "E4") (pinfunction "E4_E4") (pintype "passive"))
      (node (ref "J3") (pin "E6") (pinfunction "E6_E6") (pintype "passive"))
      (node (ref "J3") (pin "E8") (pinfunction "E8_E8") (pintype "passive"))
      (node (ref "J3") (pin "H2") (pinfunction "H2_H2") (pintype "passive"))
      (node (ref "J3") (pin "H4") (pinfunction "H4_H4") (pintype "passive"))
      (node (ref "J3") (pin "H6") (pinfunction "H6_H6") (pintype "passive"))
      (node (ref "J3") (pin "H8") (pinfunction "H8_H8") (pintype "passive"))
      (node (ref "J3") (pin "K2") (pinfunction "K2_K2") (pintype "passive"))
      (node (ref "J3") (pin "K4") (pinfunction "K4_K4") (pintype "passive"))
      (node (ref "J3") (pin "K6") (pinfunction "K6_K6") (pintype "passive"))
      (node (ref "J3") (pin "K8") (pinfunction "K8_K8") (pintype "passive"))
    )
    (net (code "242") (name "PGND") (class "Default")
      (node (ref "J1") (pin "MH1") (pinfunction "Shield_MH1") (pintype "passive"))
      (node (ref "J1") (pin "MH10") (pinfunction "Shield_MH10") (pintype "passive"))
      (node (ref "J1") (pin "MH11") (pinfunction "Shield_MH11") (pintype "passive"))
      (node (ref "J1") (pin "MH12") (pinfunction "Shield_MH12") (pintype "passive"))
      (node (ref "J1") (pin "MH13") (pinfunction "Shield_MH13") (pintype "passive"))
      (node (ref "J1") (pin "MH14") (pinfunction "Shield_MH14") (pintype "passive"))
      (node (ref "J1") (pin "MH15") (pinfunction "Shield_MH15") (pintype "passive"))
      (node (ref "J1") (pin "MH16") (pinfunction "Shield_MH16") (pintype "passive"))
      (node (ref "J1") (pin "MH2") (pinfunction "Shield_MH2") (pintype "passive"))
      (node (ref "J1") (pin "MH3") (pinfunction "Shield_MH3") (pintype "passive"))
      (node (ref "J1") (pin "MH4") (pinfunction "Shield_MH4") (pintype "passive"))
      (node (ref "J1") (pin "MH5") (pinfunction "Shield_MH5") (pintype "passive"))
      (node (ref "J1") (pin "MH6") (pinfunction "Shield_MH6") (pintype "passive"))
      (node (ref "J1") (pin "MH7") (pinfunction "Shield_MH7") (pintype "passive"))
      (node (ref "J1") (pin "MH8") (pinfunction "Shield_MH8") (pintype "passive"))
      (node (ref "J1") (pin "MH9") (pinfunction "Shield_MH9") (pintype "passive"))
      (node (ref "J2") (pin "MH1") (pinfunction "Shield_MH1") (pintype "passive"))
      (node (ref "J2") (pin "MH10") (pinfunction "Shield_MH10") (pintype "passive"))
      (node (ref "J2") (pin "MH11") (pinfunction "Shield_MH11") (pintype "passive"))
      (node (ref "J2") (pin "MH12") (pinfunction "Shield_MH12") (pintype "passive"))
      (node (ref "J2") (pin "MH13") (pinfunction "Shield_MH13") (pintype "passive"))
      (node (ref "J2") (pin "MH14") (pinfunction "Shield_MH14") (pintype "passive"))
      (node (ref "J2") (pin "MH15") (pinfunction "Shield_MH15") (pintype "passive"))
      (node (ref "J2") (pin "MH16") (pinfunction "Shield_MH16") (pintype "passive"))
      (node (ref "J2") (pin "MH2") (pinfunction "Shield_MH2") (pintype "passive"))
      (node (ref "J2") (pin "MH3") (pinfunction "Shield_MH3") (pintype "passive"))
      (node (ref "J2") (pin "MH4") (pinfunction "Shield_MH4") (pintype "passive"))
      (node (ref "J2") (pin "MH5") (pinfunction "Shield_MH5") (pintype "passive"))
      (node (ref "J2") (pin "MH6") (pinfunction "Shield_MH6") (pintype "passive"))
      (node (ref "J2") (pin "MH7") (pinfunction "Shield_MH7") (pintype "passive"))
      (node (ref "J2") (pin "MH8") (pinfunction "Shield_MH8") (pintype "passive"))
      (node (ref "J2") (pin "MH9") (pinfunction "Shield_MH9") (pintype "passive"))
      (node (ref "J3") (pin "MH1") (pinfunction "Shield_MH1") (pintype "passive"))
      (node (ref "J3") (pin "MH10") (pinfunction "Shield_MH10") (pintype "passive"))
      (node (ref "J3") (pin "MH11") (pinfunction "Shield_MH11") (pintype "passive"))
      (node (ref "J3") (pin "MH12") (pinfunction "Shield_MH12") (pintype "passive"))
      (node (ref "J3") (pin "MH13") (pinfunction "Shield_MH13") (pintype "passive"))
      (node (ref "J3") (pin "MH14") (pinfunction "Shield_MH14") (pintype "passive"))
      (node (ref "J3") (pin "MH15") (pinfunction "Shield_MH15") (pintype "passive"))
      (node (ref "J3") (pin "MH16") (pinfunction "Shield_MH16") (pintype "passive"))
      (node (ref "J3") (pin "MH2") (pinfunction "Shield_MH2") (pintype "passive"))
      (node (ref "J3") (pin "MH3") (pinfunction "Shield_MH3") (pintype "passive"))
      (node (ref "J3") (pin "MH4") (pinfunction "Shield_MH4") (pintype "passive"))
      (node (ref "J3") (pin "MH5") (pinfunction "Shield_MH5") (pintype "passive"))
      (node (ref "J3") (pin "MH6") (pinfunction "Shield_MH6") (pintype "passive"))
      (node (ref "J3") (pin "MH7") (pinfunction "Shield_MH7") (pintype "passive"))
      (node (ref "J3") (pin "MH8") (pinfunction "Shield_MH8") (pintype "passive"))
      (node (ref "J3") (pin "MH9") (pinfunction "Shield_MH9") (pintype "passive"))
    )
  )
)
